# MX.net
KiCad netlist of a schematic drawn in Altium Designer
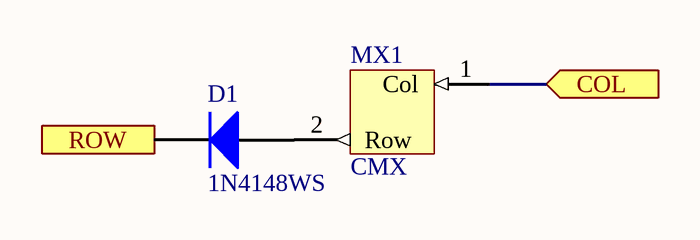
[diagram p0: MX.SchDoc]

(export (version "E")
  (design (tool "Eeschema 10.0.6"))
  (components
    (comp (ref "D1")
      (value "1N4148WS")
      (footprint "DIOD-SOD323-2-A_V")
      (description "Fast Switching Diode, 75 V, 0.3 A, -65 to 150 degC, 2-Pin SOD323, RoHS, Tape and Reel")
      (libsource (lib "Altium Content Vault") (part "D-AK-2"))
    )
    (comp (ref "MX1")
      (value "CMX")
      (footprint "MX")
      (description "Cherry MX Footprint")
      (libsource (lib "Skayboard") (part "MX"))
    )
  )
  (nets
    (net (code "1") (name "/COL") (class "Default")
      (node (ref "MX1") (pin "1") (pinfunction "Col_1") (pintype "input"))
    )
    (net (code "2") (name "/ROW") (class "Default")
      (node (ref "D1") (pin "2") (pinfunction "K_2") (pintype "passive"))
    )
    (net (code "3") (name "Net-(D1-A)") (class "Default")
      (node (ref "D1") (pin "1") (pinfunction "A_1") (pintype "passive"))
      (node (ref "MX1") (pin "2") (pinfunction "Row_2") (pintype "output"))
    )
  )
)
